# CANreader-XL.net
KiCad netlist of a schematic drawn in EAGLE
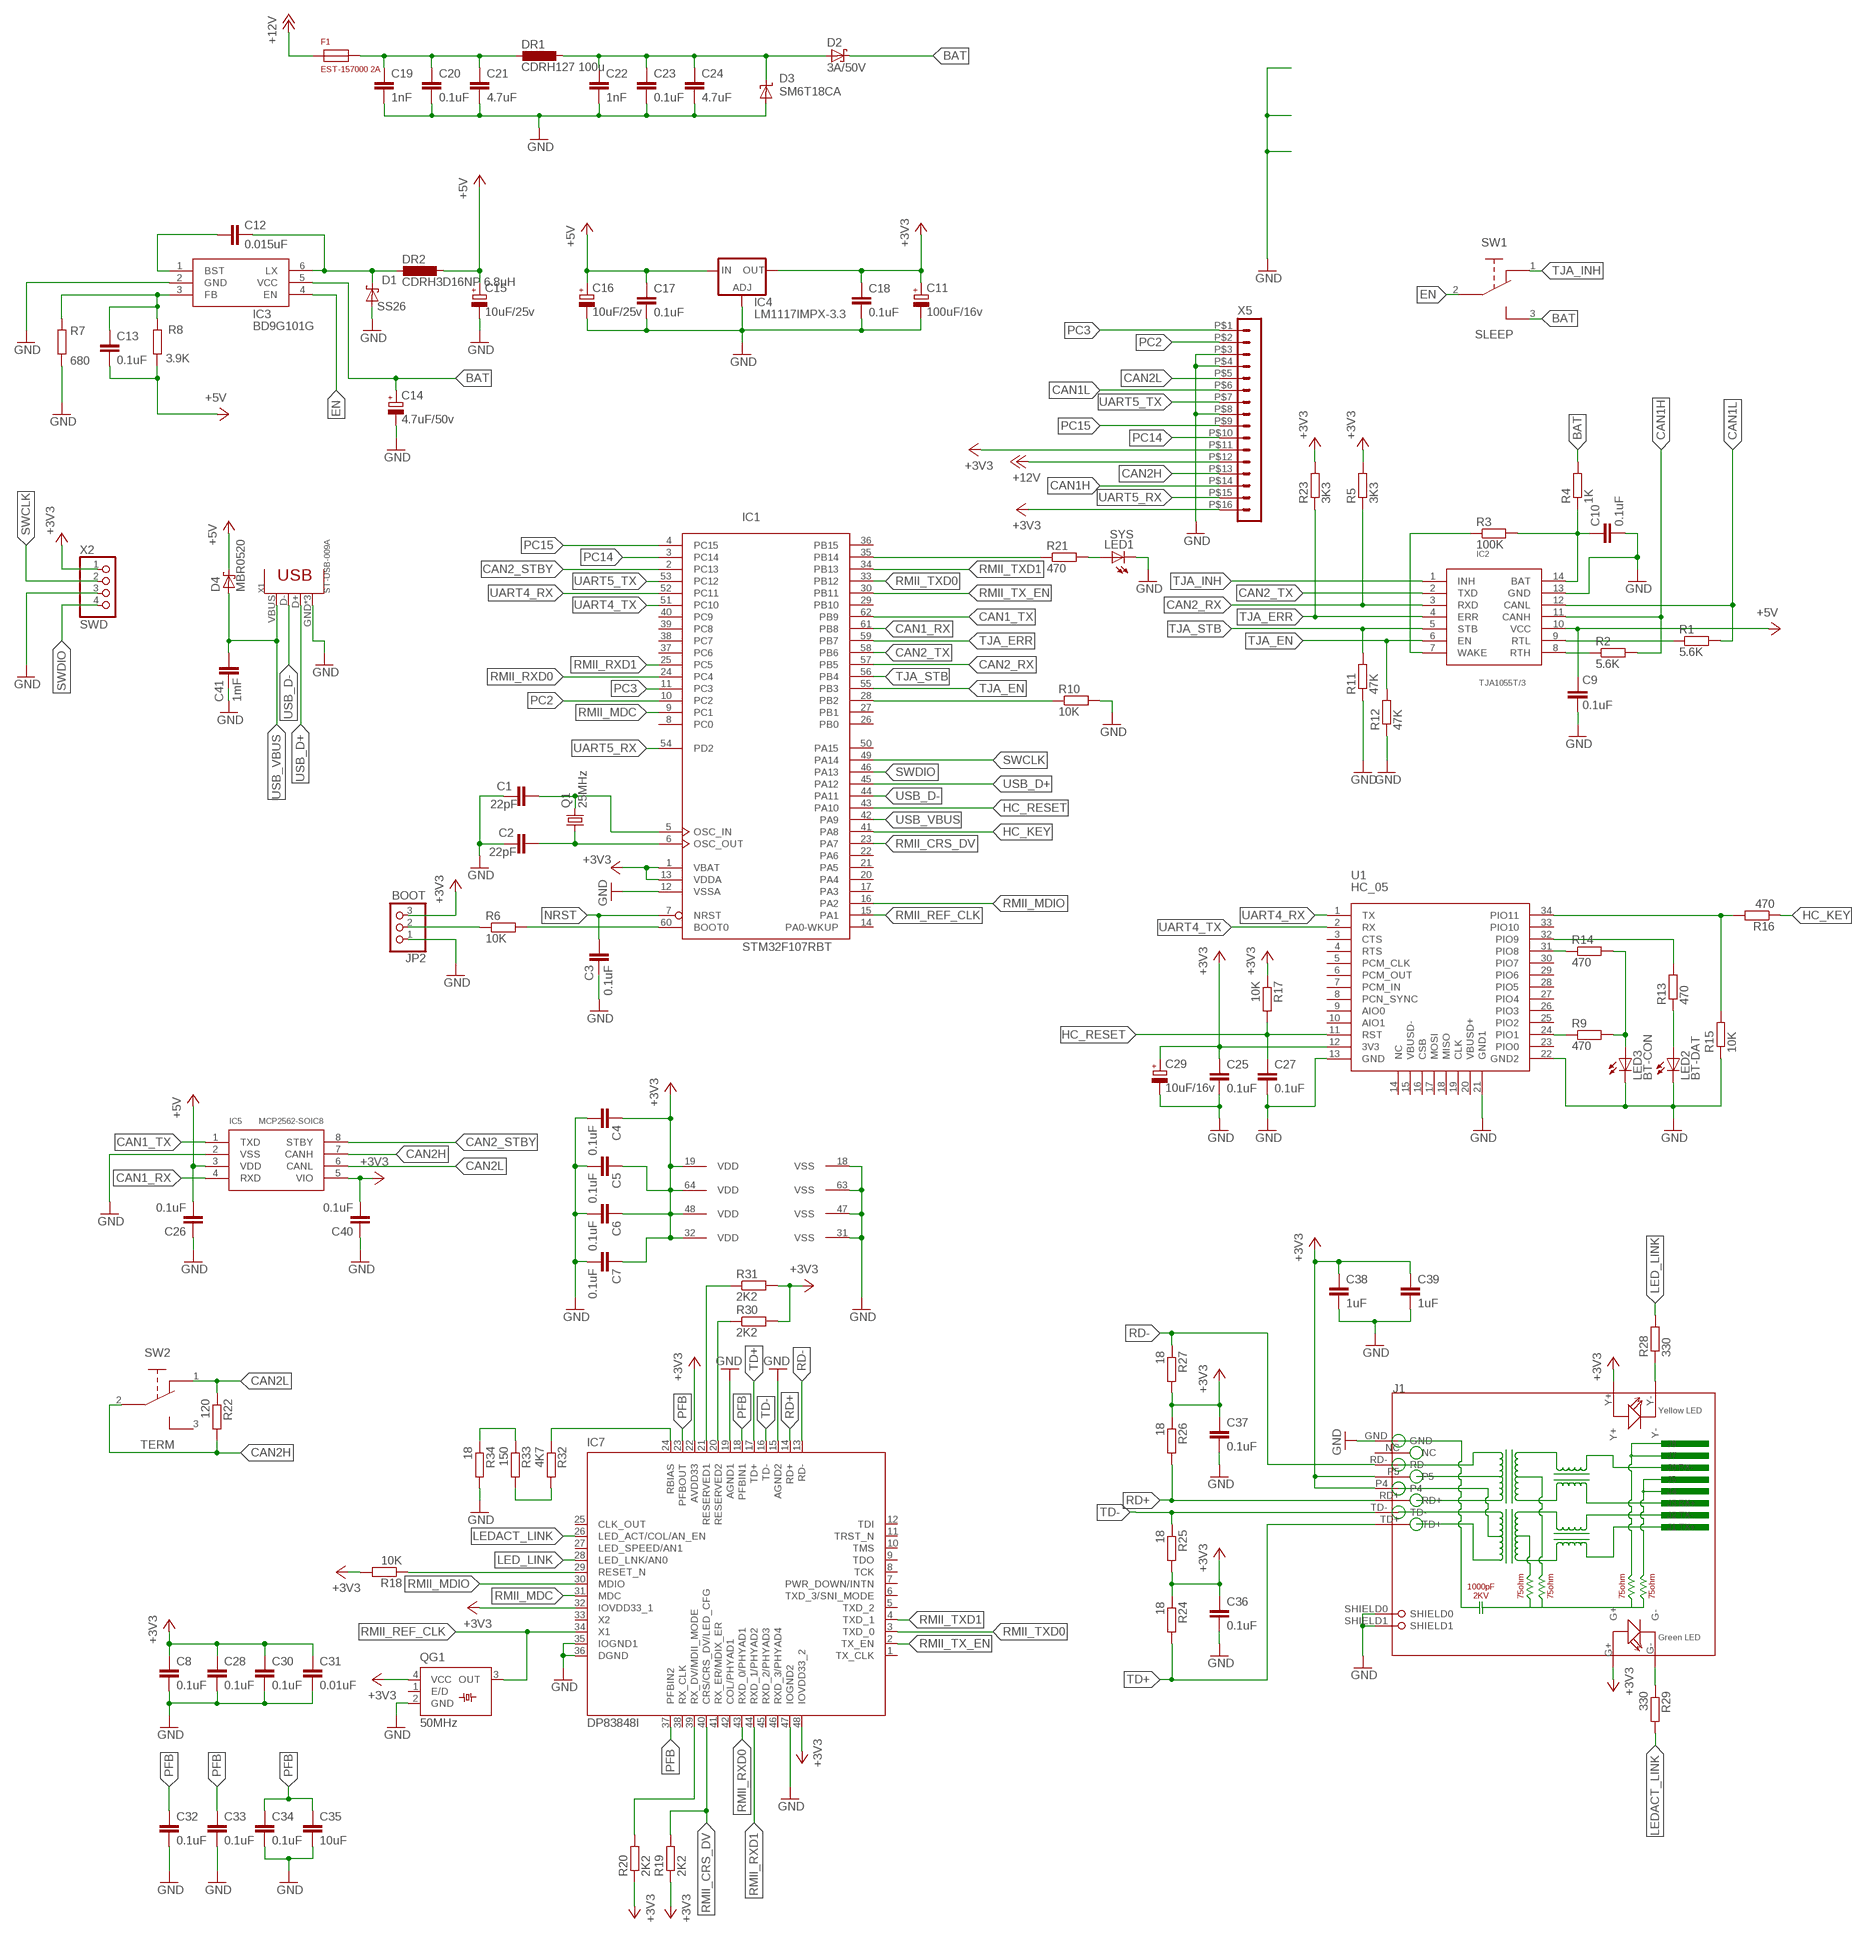
[diagram p0: schematic, sheet 1]

(export (version "E")
  (design (tool "Eeschema 10.0.6"))
  (components
    (comp (ref "C1")
      (value "22pF")
      (footprint "eagle-import:C0805")
      (libsource (lib "eagle-import") (part "C-EUC0805"))
    )
    (comp (ref "C2")
      (value "22pF")
      (footprint "eagle-import:C0805")
      (libsource (lib "eagle-import") (part "C-EUC0805"))
    )
    (comp (ref "C3")
      (value "0.1uF")
      (footprint "eagle-import:C0805")
      (libsource (lib "eagle-import") (part "C-EUC0805"))
    )
    (comp (ref "C4")
      (value "0.1uF")
      (footprint "eagle-import:C0805")
      (libsource (lib "eagle-import") (part "C-EUC0805"))
    )
    (comp (ref "C5")
      (value "0.1uF")
      (footprint "eagle-import:C0805")
      (libsource (lib "eagle-import") (part "C-EUC0805"))
    )
    (comp (ref "C6")
      (value "0.1uF")
      (footprint "eagle-import:C0805")
      (libsource (lib "eagle-import") (part "C-EUC0805"))
    )
    (comp (ref "C7")
      (value "0.1uF")
      (footprint "eagle-import:C0805")
      (libsource (lib "eagle-import") (part "C-EUC0805"))
    )
    (comp (ref "C8")
      (value "0.1uF")
      (footprint "eagle-import:C0805")
      (libsource (lib "eagle-import") (part "C-EUC0805"))
    )
    (comp (ref "C9")
      (value "0.1uF")
      (footprint "eagle-import:C0805")
      (libsource (lib "eagle-import") (part "C-EUC0805"))
    )
    (comp (ref "C10")
      (value "0.1uF")
      (footprint "eagle-import:C0805")
      (libsource (lib "eagle-import") (part "C-EUC0805"))
    )
    (comp (ref "C11")
      (value "100uF/16v")
      (footprint "eagle-import:SMC_D")
      (libsource (lib "eagle-import") (part "CPOL-EUSMCD"))
    )
    (comp (ref "C12")
      (value "0.015uF")
      (footprint "eagle-import:C0805")
      (libsource (lib "eagle-import") (part "C-EUC0805"))
    )
    (comp (ref "C13")
      (value "0.1uF")
      (footprint "eagle-import:C0805")
      (libsource (lib "eagle-import") (part "C-EUC0805"))
    )
    (comp (ref "C14")
      (value "4.7uF/50v")
      (footprint "eagle-import:153CLV-0505")
      (libsource (lib "eagle-import") (part "CPOL-EU153CLV-0505"))
    )
    (comp (ref "C15")
      (value "10uF/25v")
      (footprint "eagle-import:SMC_C")
      (libsource (lib "eagle-import") (part "CPOL-EUSMCC"))
    )
    (comp (ref "C16")
      (value "10uF/25v")
      (footprint "eagle-import:SMC_C")
      (libsource (lib "eagle-import") (part "CPOL-EUSMCC"))
    )
    (comp (ref "C17")
      (value "0.1uF")
      (footprint "eagle-import:C0805")
      (libsource (lib "eagle-import") (part "C-EUC0805"))
    )
    (comp (ref "C18")
      (value "0.1uF")
      (footprint "eagle-import:C0805")
      (libsource (lib "eagle-import") (part "C-EUC0805"))
    )
    (comp (ref "C19")
      (value "1nF")
      (footprint "eagle-import:C0805")
      (libsource (lib "eagle-import") (part "C-EUC0805"))
    )
    (comp (ref "C20")
      (value "0.1uF")
      (footprint "eagle-import:C0805")
      (libsource (lib "eagle-import") (part "C-EUC0805"))
    )
    (comp (ref "C21")
      (value "4.7uF")
      (footprint "eagle-import:C0805")
      (libsource (lib "eagle-import") (part "C-EUC0805"))
    )
    (comp (ref "C22")
      (value "1nF")
      (footprint "eagle-import:C0805")
      (libsource (lib "eagle-import") (part "C-EUC0805"))
    )
    (comp (ref "C23")
      (value "0.1uF")
      (footprint "eagle-import:C0805")
      (libsource (lib "eagle-import") (part "C-EUC0805"))
    )
    (comp (ref "C24")
      (value "4.7uF")
      (footprint "eagle-import:C0805")
      (libsource (lib "eagle-import") (part "C-EUC0805"))
    )
    (comp (ref "C25")
      (value "0.1uF")
      (footprint "eagle-import:C0805")
      (libsource (lib "eagle-import") (part "C-EUC0805"))
    )
    (comp (ref "C26")
      (value "0.1uF")
      (footprint "eagle-import:C0805")
      (libsource (lib "eagle-import") (part "C-EUC0805"))
    )
    (comp (ref "C27")
      (value "0.1uF")
      (footprint "eagle-import:C0805")
      (libsource (lib "eagle-import") (part "C-EUC0805"))
    )
    (comp (ref "C28")
      (value "0.1uF")
      (footprint "eagle-import:C0805")
      (libsource (lib "eagle-import") (part "C-EUC0805"))
    )
    (comp (ref "C29")
      (value "10uF/16v")
      (footprint "eagle-import:SMC_A")
      (libsource (lib "eagle-import") (part "CPOL-EUSMCA"))
    )
    (comp (ref "C30")
      (value "0.1uF")
      (footprint "eagle-import:C0805")
      (libsource (lib "eagle-import") (part "C-EUC0805"))
    )
    (comp (ref "C31")
      (value "0.01uF")
      (footprint "eagle-import:C0805")
      (libsource (lib "eagle-import") (part "C-EUC0805"))
    )
    (comp (ref "C32")
      (value "0.1uF")
      (footprint "eagle-import:C0805")
      (libsource (lib "eagle-import") (part "C-EUC0805"))
    )
    (comp (ref "C33")
      (value "0.1uF")
      (footprint "eagle-import:C0805")
      (libsource (lib "eagle-import") (part "C-EUC0805"))
    )
    (comp (ref "C34")
      (value "0.1uF")
      (footprint "eagle-import:C0805")
      (libsource (lib "eagle-import") (part "C-EUC0805"))
    )
    (comp (ref "C35")
      (value "10uF")
      (footprint "eagle-import:C0805")
      (libsource (lib "eagle-import") (part "C-EUC0805"))
    )
    (comp (ref "C36")
      (value "0.1uF")
      (footprint "eagle-import:C0805")
      (libsource (lib "eagle-import") (part "C-EUC0805"))
    )
    (comp (ref "C37")
      (value "0.1uF")
      (footprint "eagle-import:C0805")
      (libsource (lib "eagle-import") (part "C-EUC0805"))
    )
    (comp (ref "C38")
      (value "1uF")
      (footprint "eagle-import:C0805")
      (libsource (lib "eagle-import") (part "C-EUC0805"))
    )
    (comp (ref "C39")
      (value "1uF")
      (footprint "eagle-import:C0805")
      (libsource (lib "eagle-import") (part "C-EUC0805"))
    )
    (comp (ref "C40")
      (value "0.1uF")
      (footprint "eagle-import:C0805")
      (libsource (lib "eagle-import") (part "C-EUC0805"))
    )
    (comp (ref "C41")
      (value "1mF")
      (footprint "eagle-import:C0805")
      (libsource (lib "eagle-import") (part "C-EUC0805"))
    )
    (comp (ref "D1")
      (value "SS26")
      (footprint "eagle-import:SMB")
      (libsource (lib "eagle-import") (part "SCHOTTKY-DIODESMD"))
    )
    (comp (ref "D2")
      (value "3A/50V")
      (footprint "eagle-import:SMC")
      (libsource (lib "eagle-import") (part "diode_SCHOTTKY-DIODESMC"))
    )
    (comp (ref "D3")
      (value "SM6T18CA")
      (footprint "eagle-import:SMBJ")
      (libsource (lib "eagle-import") (part "SUPPRESSOR-SMBJ"))
    )
    (comp (ref "D4")
      (value "MBR0520")
      (footprint "eagle-import:SOD123")
      (libsource (lib "eagle-import") (part "MBR0520"))
    )
    (comp (ref "DR1")
      (value "CDRH127 100u")
      (footprint "eagle-import:MS85")
      (libsource (lib "eagle-import") (part "CDRH127"))
    )
    (comp (ref "DR2")
      (value "CDRH3D16NP 6.8uH")
      (footprint "eagle-import:CDRH3D16NP")
      (libsource (lib "eagle-import") (part "CDRH3D16NP"))
    )
    (comp (ref "F1")
      (value "EST-157000 2A")
      (footprint "eagle-import:FUSE")
      (libsource (lib "eagle-import") (part "FUSE"))
    )
    (comp (ref "IC1")
      (value "STM32F107RBT")
      (footprint "eagle-import:LQFP64")
      (libsource (lib "eagle-import") (part "STM32F107RTB"))
    )
    (comp (ref "IC2")
      (value "TJA1055T/3")
      (footprint "eagle-import:SO-14W")
      (libsource (lib "eagle-import") (part "TJA1054T"))
    )
    (comp (ref "IC3")
      (value "BD9G101G")
      (footprint "eagle-import:SSOP6")
      (libsource (lib "eagle-import") (part "BD9G101G"))
    )
    (comp (ref "IC4")
      (value "LM1117IMPX-3.3")
      (footprint "eagle-import:SOT223")
      (libsource (lib "eagle-import") (part "LM1117IMPX-3.3"))
    )
    (comp (ref "IC5")
      (value "MCP2562-SOIC8")
      (footprint "eagle-import:SOIC8-1.27-5X4MM")
      (libsource (lib "eagle-import") (part "MCP2562-SOIC8"))
    )
    (comp (ref "IC7")
      (value "DP83848I")
      (footprint "eagle-import:LQFP48")
      (fields (field (name "MPN") "DP83848VYB"))
      (libsource (lib "eagle-import") (part "DP83848I"))
    )
    (comp (ref "J1")
      (value "RJ45-HR911105A-HR911105A")
      (footprint "eagle-import:RJ45")
      (libsource (lib "eagle-import") (part "RJ45-HR911105A-HR911105A"))
    )
    (comp (ref "JP2")
      (value "BOOT")
      (footprint "eagle-import:1X03")
      (libsource (lib "eagle-import") (part "PINHD-1X3"))
    )
    (comp (ref "LED1")
      (value "SYS")
      (footprint "eagle-import:LED3MM")
      (libsource (lib "eagle-import") (part "LED3MM"))
    )
    (comp (ref "LED2")
      (value "BT-DAT")
      (footprint "eagle-import:LED3MM")
      (libsource (lib "eagle-import") (part "LED3MM"))
    )
    (comp (ref "LED3")
      (value "BT-CON")
      (footprint "eagle-import:LED3MM")
      (libsource (lib "eagle-import") (part "LED3MM"))
    )
    (comp (ref "Q1")
      (value "25MHz")
      (footprint "eagle-import:HC49_S")
      (libsource (lib "eagle-import") (part "CRYSTALHC49S"))
    )
    (comp (ref "QG1")
      (value "50MHz")
      (footprint "eagle-import:SM77H")
      (libsource (lib "eagle-import") (part "SM77H"))
    )
    (comp (ref "R1")
      (value "5.6K")
      (footprint "eagle-import:R0805")
      (libsource (lib "eagle-import") (part "R-EU_R0805"))
    )
    (comp (ref "R2")
      (value "5.6K")
      (footprint "eagle-import:R0805")
      (libsource (lib "eagle-import") (part "R-EU_R0805"))
    )
    (comp (ref "R3")
      (value "100K")
      (footprint "eagle-import:R0805")
      (libsource (lib "eagle-import") (part "R-EU_R0805"))
    )
    (comp (ref "R4")
      (value "1K")
      (footprint "eagle-import:R0805")
      (libsource (lib "eagle-import") (part "R-EU_R0805"))
    )
    (comp (ref "R5")
      (value "3K3")
      (footprint "eagle-import:R0805")
      (libsource (lib "eagle-import") (part "R-EU_R0805"))
    )
    (comp (ref "R6")
      (value "10K")
      (footprint "eagle-import:R0805")
      (libsource (lib "eagle-import") (part "R-EU_R0805"))
    )
    (comp (ref "R7")
      (value "680")
      (footprint "eagle-import:R0805")
      (libsource (lib "eagle-import") (part "R-EU_R0805"))
    )
    (comp (ref "R8")
      (value "3.9K")
      (footprint "eagle-import:R0805")
      (libsource (lib "eagle-import") (part "R-EU_R0805"))
    )
    (comp (ref "R9")
      (value "470")
      (footprint "eagle-import:R0805")
      (libsource (lib "eagle-import") (part "R-EU_R0805"))
    )
    (comp (ref "R10")
      (value "10K")
      (footprint "eagle-import:R0805")
      (libsource (lib "eagle-import") (part "R-EU_R0805"))
    )
    (comp (ref "R11")
      (value "47K")
      (footprint "eagle-import:R0805")
      (libsource (lib "eagle-import") (part "R-EU_R0805"))
    )
    (comp (ref "R12")
      (value "47K")
      (footprint "eagle-import:R0805")
      (libsource (lib "eagle-import") (part "R-EU_R0805"))
    )
    (comp (ref "R13")
      (value "470")
      (footprint "eagle-import:R0805")
      (libsource (lib "eagle-import") (part "R-EU_R0805"))
    )
    (comp (ref "R14")
      (value "470")
      (footprint "eagle-import:R0805")
      (libsource (lib "eagle-import") (part "R-EU_R0805"))
    )
    (comp (ref "R15")
      (value "10K")
      (footprint "eagle-import:R0805")
      (libsource (lib "eagle-import") (part "R-EU_R0805"))
    )
    (comp (ref "R16")
      (value "470")
      (footprint "eagle-import:R0805")
      (libsource (lib "eagle-import") (part "R-EU_R0805"))
    )
    (comp (ref "R17")
      (value "10K")
      (footprint "eagle-import:R0805")
      (libsource (lib "eagle-import") (part "R-EU_R0805"))
    )
    (comp (ref "R18")
      (value "10K")
      (footprint "eagle-import:R0805")
      (libsource (lib "eagle-import") (part "R-EU_R0805"))
    )
    (comp (ref "R19")
      (value "2K2")
      (footprint "eagle-import:R0805")
      (libsource (lib "eagle-import") (part "R-EU_R0805"))
    )
    (comp (ref "R20")
      (value "2K2")
      (footprint "eagle-import:R0805")
      (libsource (lib "eagle-import") (part "R-EU_R0805"))
    )
    (comp (ref "R21")
      (value "470")
      (footprint "eagle-import:R0805")
      (libsource (lib "eagle-import") (part "R-EU_R0805"))
    )
    (comp (ref "R22")
      (value "120")
      (footprint "eagle-import:R0805")
      (libsource (lib "eagle-import") (part "R-EU_R0805"))
    )
    (comp (ref "R23")
      (value "3K3")
      (footprint "eagle-import:R0805")
      (libsource (lib "eagle-import") (part "R-EU_R0805"))
    )
    (comp (ref "R24")
      (value "18")
      (footprint "eagle-import:R0805")
      (libsource (lib "eagle-import") (part "R-EU_R0805"))
    )
    (comp (ref "R25")
      (value "18")
      (footprint "eagle-import:R0805")
      (libsource (lib "eagle-import") (part "R-EU_R0805"))
    )
    (comp (ref "R26")
      (value "18")
      (footprint "eagle-import:R0805")
      (libsource (lib "eagle-import") (part "R-EU_R0805"))
    )
    (comp (ref "R27")
      (value "18")
      (footprint "eagle-import:R0805")
      (libsource (lib "eagle-import") (part "R-EU_R0805"))
    )
    (comp (ref "R28")
      (value "330")
      (footprint "eagle-import:R0805")
      (libsource (lib "eagle-import") (part "R-EU_R0805"))
    )
    (comp (ref "R29")
      (value "330")
      (footprint "eagle-import:R0805")
      (libsource (lib "eagle-import") (part "R-EU_R0805"))
    )
    (comp (ref "R30")
      (value "2K2")
      (footprint "eagle-import:R0805")
      (libsource (lib "eagle-import") (part "R-EU_R0805"))
    )
    (comp (ref "R31")
      (value "2K2")
      (footprint "eagle-import:R0805")
      (libsource (lib "eagle-import") (part "R-EU_R0805"))
    )
    (comp (ref "R32")
      (value "4K7")
      (footprint "eagle-import:R0805")
      (libsource (lib "eagle-import") (part "R-EU_R0805"))
    )
    (comp (ref "R33")
      (value "150")
      (footprint "eagle-import:R0805")
      (libsource (lib "eagle-import") (part "R-EU_R0805"))
    )
    (comp (ref "R34")
      (value "18")
      (footprint "eagle-import:R0805")
      (libsource (lib "eagle-import") (part "R-EU_R0805"))
    )
    (comp (ref "SW1")
      (value "SLEEP")
      (footprint "eagle-import:SS12F27")
      (libsource (lib "eagle-import") (part "SS12F27"))
    )
    (comp (ref "SW2")
      (value "TERM")
      (footprint "eagle-import:SS12F27")
      (libsource (lib "eagle-import") (part "SS12F27"))
    )
    (comp (ref "U1")
      (value "HC_05")
      (footprint "eagle-import:BLUETOOTH_SMD")
      (libsource (lib "eagle-import") (part "HC_05"))
    )
    (comp (ref "X1")
      (value "ST-USB-009A")
      (footprint "eagle-import:USB4+2-2.5-90D")
      (libsource (lib "eagle-import") (part "DIP-USB-B-TYPE-FMAL(4+2P-2.5-90D)"))
    )
    (comp (ref "X2")
      (value "SWD")
      (footprint "eagle-import:1X04")
      (libsource (lib "eagle-import") (part "PINHD-1X4"))
    )
    (comp (ref "X5")
      (value "HEADER_POS16_43045-1600")
      (footprint "eagle-import:43045-1600")
      (libsource (lib "eagle-import") (part "HEADER_POS16_?43045-1600"))
    )
  )
  (nets
    (net (code "1") (name "+3V3") (class "Default")
      (node (ref "C11") (pin "+") (pinfunction "+_+") (pintype "passive"))
      (node (ref "C18") (pin "1") (pinfunction "1_1") (pintype "passive"))
      (node (ref "C25") (pin "1") (pinfunction "1_1") (pintype "passive"))
      (node (ref "C28") (pin "1") (pinfunction "1_1") (pintype "passive"))
      (node (ref "C29") (pin "+") (pinfunction "+_+") (pintype "passive"))
      (node (ref "C30") (pin "1") (pinfunction "1_1") (pintype "passive"))
      (node (ref "C31") (pin "1") (pinfunction "1_1") (pintype "passive"))
      (node (ref "C36") (pin "1") (pinfunction "1_1") (pintype "passive"))
      (node (ref "C37") (pin "1") (pinfunction "1_1") (pintype "passive"))
      (node (ref "C38") (pin "1") (pinfunction "1_1") (pintype "passive"))
      (node (ref "C39") (pin "1") (pinfunction "1_1") (pintype "passive"))
      (node (ref "C4") (pin "1") (pinfunction "1_1") (pintype "passive"))
      (node (ref "C40") (pin "2") (pinfunction "2_2") (pintype "passive"))
      (node (ref "C5") (pin "1") (pinfunction "1_1") (pintype "passive"))
      (node (ref "C6") (pin "1") (pinfunction "1_1") (pintype "passive"))
      (node (ref "C7") (pin "1") (pinfunction "1_1") (pintype "passive"))
      (node (ref "C8") (pin "1") (pinfunction "1_1") (pintype "passive"))
      (node (ref "IC1") (pin "1") (pinfunction "VBAT_1") (pintype "power_in"))
      (node (ref "IC1") (pin "13") (pinfunction "VDDA_13") (pintype "power_in"))
      (node (ref "IC1") (pin "19") (pinfunction "VDD_19") (pintype "power_in"))
      (node (ref "IC1") (pin "32") (pinfunction "VDD_32") (pintype "power_in"))
      (node (ref "IC1") (pin "48") (pinfunction "VDD_48") (pintype "power_in"))
      (node (ref "IC1") (pin "64") (pinfunction "VDD_64") (pintype "power_in"))
      (node (ref "IC4") (pin "2") (pinfunction "OUT_2") (pintype "passive"))
      (node (ref "IC4") (pin "4") (pinfunction "OUT_4") (pintype "passive"))
      (node (ref "IC5") (pin "5") (pinfunction "VIO_5") (pintype "power_in"))
      (node (ref "IC7") (pin "22") (pinfunction "AVDD33_22") (pintype "power_in"))
      (node (ref "IC7") (pin "32") (pinfunction "IOVDD33_1_32") (pintype "power_in"))
      (node (ref "IC7") (pin "48") (pinfunction "IOVDD33_2_48") (pintype "power_in"))
      (node (ref "J1") (pin "G+") (pinfunction "G+_G+") (pintype "bidirectional"))
      (node (ref "J1") (pin "P4") (pinfunction "P4_P4") (pintype "bidirectional"))
      (node (ref "J1") (pin "P5") (pinfunction "P5_P5") (pintype "bidirectional"))
      (node (ref "J1") (pin "Y+") (pinfunction "Y+_Y+") (pintype "bidirectional"))
      (node (ref "JP2") (pin "3") (pinfunction "3_3") (pintype "passive"))
      (node (ref "QG1") (pin "4") (pinfunction "VCC_4") (pintype "power_in"))
      (node (ref "R17") (pin "1") (pinfunction "1_1") (pintype "passive"))
      (node (ref "R18") (pin "2") (pinfunction "2_2") (pintype "passive"))
      (node (ref "R19") (pin "1") (pinfunction "1_1") (pintype "passive"))
      (node (ref "R20") (pin "1") (pinfunction "1_1") (pintype "passive"))
      (node (ref "R23") (pin "2") (pinfunction "2_2") (pintype "passive"))
      (node (ref "R24") (pin "1") (pinfunction "1_1") (pintype "passive"))
      (node (ref "R25") (pin "2") (pinfunction "2_2") (pintype "passive"))
      (node (ref "R26") (pin "1") (pinfunction "1_1") (pintype "passive"))
      (node (ref "R27") (pin "2") (pinfunction "2_2") (pintype "passive"))
      (node (ref "R30") (pin "2") (pinfunction "2_2") (pintype "passive"))
      (node (ref "R31") (pin "2") (pinfunction "2_2") (pintype "passive"))
      (node (ref "R5") (pin "2") (pinfunction "2_2") (pintype "passive"))
      (node (ref "U1") (pin "12") (pinfunction "3V3_12") (pintype "bidirectional"))
      (node (ref "X2") (pin "1") (pinfunction "1_1") (pintype "passive"))
      (node (ref "X5") (pin "P$11") (pinfunction "11_P$11") (pintype "passive"))
      (node (ref "X5") (pin "P$16") (pinfunction "16_P$16") (pintype "passive"))
    )
    (net (code "2") (name "+5V") (class "Default")
      (node (ref "C13") (pin "2") (pinfunction "2_2") (pintype "passive"))
      (node (ref "C15") (pin "+") (pinfunction "+_+") (pintype "passive"))
      (node (ref "C16") (pin "+") (pinfunction "+_+") (pintype "passive"))
      (node (ref "C17") (pin "1") (pinfunction "1_1") (pintype "passive"))
      (node (ref "C26") (pin "2") (pinfunction "2_2") (pintype "passive"))
      (node (ref "C9") (pin "1") (pinfunction "1_1") (pintype "passive"))
      (node (ref "D4") (pin "C") (pinfunction "C_C") (pintype "passive"))
      (node (ref "DR2") (pin "P$2") (pinfunction "2_P$2") (pintype "passive"))
      (node (ref "IC2") (pin "10") (pinfunction "VCC_10") (pintype "power_in"))
      (node (ref "IC4") (pin "3") (pinfunction "IN_3") (pintype "input"))
      (node (ref "IC5") (pin "3") (pinfunction "VDD_3") (pintype "power_in"))
      (node (ref "R8") (pin "1") (pinfunction "1_1") (pintype "passive"))
    )
    (net (code "3") (name "+12V") (class "Default")
      (node (ref "F1") (pin "P$1") (pinfunction "1_P$1") (pintype "power_in"))
      (node (ref "X5") (pin "P$12") (pinfunction "12_P$12") (pintype "passive"))
    )
    (net (code "4") (name "BAT") (class "Default")
      (node (ref "C14") (pin "+") (pinfunction "+_+") (pintype "passive"))
      (node (ref "D2") (pin "C") (pinfunction "C_C") (pintype "passive"))
      (node (ref "IC3") (pin "5") (pinfunction "VCC_5") (pintype "power_in"))
      (node (ref "R4") (pin "2") (pinfunction "2_2") (pintype "passive"))
      (node (ref "SW1") (pin "3") (pinfunction "3_3") (pintype "bidirectional"))
    )
    (net (code "5") (name "CAN1H") (class "Default")
      (node (ref "IC2") (pin "11") (pinfunction "CANH_11") (pintype "bidirectional"))
      (node (ref "R2") (pin "2") (pinfunction "2_2") (pintype "passive"))
      (node (ref "X5") (pin "P$14") (pinfunction "14_P$14") (pintype "passive"))
    )
    (net (code "6") (name "CAN1L") (class "Default")
      (node (ref "IC2") (pin "12") (pinfunction "CANL_12") (pintype "bidirectional"))
      (node (ref "R1") (pin "2") (pinfunction "2_2") (pintype "passive"))
      (node (ref "X5") (pin "P$6") (pinfunction "6_P$6") (pintype "passive"))
    )
    (net (code "7") (name "CAN1_RX") (class "Default")
      (node (ref "IC1") (pin "61") (pinfunction "PB8_61") (pintype "bidirectional"))
      (node (ref "IC5") (pin "4") (pinfunction "RXD_4") (pintype "output"))
    )
    (net (code "8") (name "CAN1_TX") (class "Default")
      (node (ref "IC1") (pin "62") (pinfunction "PB9_62") (pintype "bidirectional"))
      (node (ref "IC5") (pin "1") (pinfunction "TXD_1") (pintype "input"))
    )
    (net (code "9") (name "CAN2H") (class "Default")
      (node (ref "IC5") (pin "7") (pinfunction "CANH_7") (pintype "bidirectional"))
      (node (ref "R22") (pin "2") (pinfunction "2_2") (pintype "passive"))
      (node (ref "SW2") (pin "2") (pinfunction "2_2") (pintype "bidirectional"))
      (node (ref "X5") (pin "P$13") (pinfunction "13_P$13") (pintype "passive"))
    )
    (net (code "10") (name "CAN2L") (class "Default")
      (node (ref "IC5") (pin "6") (pinfunction "CANL_6") (pintype "bidirectional"))
      (node (ref "R22") (pin "1") (pinfunction "1_1") (pintype "passive"))
      (node (ref "SW2") (pin "1") (pinfunction "1_1") (pintype "bidirectional"))
      (node (ref "X5") (pin "P$5") (pinfunction "5_P$5") (pintype "passive"))
    )
    (net (code "11") (name "CAN2_RX") (class "Default")
      (node (ref "IC1") (pin "57") (pinfunction "PB5_57") (pintype "bidirectional"))
      (node (ref "IC2") (pin "3") (pinfunction "RXD_3") (pintype "bidirectional"))
      (node (ref "R5") (pin "1") (pinfunction "1_1") (pintype "passive"))
    )
    (net (code "12") (name "CAN2_STBY") (class "Default")
      (node (ref "IC1") (pin "2") (pinfunction "PC13_2") (pintype "bidirectional"))
      (node (ref "IC5") (pin "8") (pinfunction "STBY_8") (pintype "input"))
    )
    (net (code "13") (name "CAN2_TX") (class "Default")
      (node (ref "IC1") (pin "58") (pinfunction "PB6_58") (pintype "bidirectional"))
      (node (ref "IC2") (pin "2") (pinfunction "TXD_2") (pintype "bidirectional"))
    )
    (net (code "14") (name "EN") (class "Default")
      (node (ref "IC3") (pin "4") (pinfunction "EN_4") (pintype "input"))
      (node (ref "SW1") (pin "2") (pinfunction "2_2") (pintype "bidirectional"))
    )
    (net (code "15") (name "GND") (class "Default")
      (node (ref "C1") (pin "2") (pinfunction "2_2") (pintype "passive"))
      (node (ref "C10") (pin "2") (pinfunction "2_2") (pintype "passive"))
      (node (ref "C11") (pin "-") (pinfunction "-_-") (pintype "passive"))
      (node (ref "C14") (pin "-") (pinfunction "-_-") (pintype "passive"))
      (node (ref "C15") (pin "-") (pinfunction "-_-") (pintype "passive"))
      (node (ref "C16") (pin "-") (pinfunction "-_-") (pintype "passive"))
      (node (ref "C17") (pin "2") (pinfunction "2_2") (pintype "passive"))
      (node (ref "C18") (pin "2") (pinfunction "2_2") (pintype "passive"))
      (node (ref "C19") (pin "2") (pinfunction "2_2") (pintype "passive"))
      (node (ref "C2") (pin "2") (pinfunction "2_2") (pintype "passive"))
      (node (ref "C20") (pin "2") (pinfunction "2_2") (pintype "passive"))
      (node (ref "C21") (pin "2") (pinfunction "2_2") (pintype "passive"))
      (node (ref "C22") (pin "2") (pinfunction "2_2") (pintype "passive"))
      (node (ref "C23") (pin "2") (pinfunction "2_2") (pintype "passive"))
      (node (ref "C24") (pin "2") (pinfunction "2_2") (pintype "passive"))
      (node (ref "C25") (pin "2") (pinfunction "2_2") (pintype "passive"))
      (node (ref "C26") (pin "1") (pinfunction "1_1") (pintype "passive"))
      (node (ref "C27") (pin "2") (pinfunction "2_2") (pintype "passive"))
      (node (ref "C28") (pin "2") (pinfunction "2_2") (pintype "passive"))
      (node (ref "C29") (pin "-") (pinfunction "-_-") (pintype "passive"))
      (node (ref "C3") (pin "1") (pinfunction "1_1") (pintype "passive"))
      (node (ref "C30") (pin "2") (pinfunction "2_2") (pintype "passive"))
      (node (ref "C31") (pin "2") (pinfunction "2_2") (pintype "passive"))
      (node (ref "C32") (pin "2") (pinfunction "2_2") (pintype "passive"))
      (node (ref "C33") (pin "2") (pinfunction "2_2") (pintype "passive"))
      (node (ref "C34") (pin "2") (pinfunction "2_2") (pintype "passive"))
      (node (ref "C35") (pin "2") (pinfunction "2_2") (pintype "passive"))
      (node (ref "C36") (pin "2") (pinfunction "2_2") (pintype "passive"))
      (node (ref "C37") (pin "2") (pinfunction "2_2") (pintype "passive"))
      (node (ref "C38") (pin "2") (pinfunction "2_2") (pintype "passive"))
      (node (ref "C39") (pin "2") (pinfunction "2_2") (pintype "passive"))
      (node (ref "C4") (pin "2") (pinfunction "2_2") (pintype "passive"))
      (node (ref "C40") (pin "1") (pinfunction "1_1") (pintype "passive"))
      (node (ref "C41") (pin "2") (pinfunction "2_2") (pintype "passive"))
      (node (ref "C5") (pin "2") (pinfunction "2_2") (pintype "passive"))
      (node (ref "C6") (pin "2") (pinfunction "2_2") (pintype "passive"))
      (node (ref "C7") (pin "2") (pinfunction "2_2") (pintype "passive"))
      (node (ref "C8") (pin "2") (pinfunction "2_2") (pintype "passive"))
      (node (ref "C9") (pin "2") (pinfunction "2_2") (pintype "passive"))
      (node (ref "D1") (pin "A") (pinfunction "A_A") (pintype "passive"))
      (node (ref "D3") (pin "A") (pinfunction "A_A") (pintype "passive"))
      (node (ref "IC1") (pin "12") (pinfunction "VSSA_12") (pintype "power_in"))
      (node (ref "IC1") (pin "18") (pinfunction "VSS_18") (pintype "power_in"))
      (node (ref "IC1") (pin "31") (pinfunction "VSS_31") (pintype "power_in"))
      (node (ref "IC1") (pin "47") (pinfunction "VSS_47") (pintype "power_in"))
      (node (ref "IC1") (pin "63") (pinfunction "VSS_63") (pintype "power_in"))
      (node (ref "IC2") (pin "13") (pinfunction "GND_13") (pintype "power_in"))
      (node (ref "IC3") (pin "2") (pinfunction "GND_2") (pintype "power_in"))
      (node (ref "IC4") (pin "1") (pinfunction "ADJ_1") (pintype "input"))
      (node (ref "IC5") (pin "2") (pinfunction "VSS_2") (pintype "power_in"))
      (node (ref "IC7") (pin "15") (pinfunction "AGND2_15") (pintype "power_in"))
      (node (ref "IC7") (pin "19") (pinfunction "AGND1_19") (pintype "power_in"))
      (node (ref "IC7") (pin "35") (pinfunction "IOGND1_35") (pintype "power_in"))
      (node (ref "IC7") (pin "36") (pinfunction "DGND_36") (pintype "power_in"))
      (node (ref "IC7") (pin "47") (pinfunction "IOGND2_47") (pintype "power_in"))
      (node (ref "J1") (pin "GND") (pinfunction "GND_GND") (pintype "bidirectional"))
      (node (ref "J1") (pin "SHIELD0") (pinfunction "SHIELD0_SHIELD0") (pintype "bidirectional"))
      (node (ref "J1") (pin "SHIELD1") (pinfunction "SHIELD1_SHIELD1") (pintype "bidirectional"))
      (node (ref "JP2") (pin "1") (pinfunction "1_1") (pintype "passive"))
      (node (ref "LED1") (pin "K") (pinfunction "C_K") (pintype "passive"))
      (node (ref "LED2") (pin "K") (pinfunction "C_K") (pintype "passive"))
      (node (ref "LED3") (pin "K") (pinfunction "C_K") (pintype "passive"))
      (node (ref "QG1") (pin "2") (pinfunction "GND_2") (pintype "power_in"))
      (node (ref "R10") (pin "2") (pinfunction "2_2") (pintype "passive"))
      (node (ref "R11") (pin "1") (pinfunction "1_1") (pintype "passive"))
      (node (ref "R12") (pin "1") (pinfunction "1_1") (pintype "passive"))
      (node (ref "R15") (pin "1") (pinfunction "1_1") (pintype "passive"))
      (node (ref "R34") (pin "2") (pinfunction "2_2") (pintype "passive"))
      (node (ref "R7") (pin "1") (pinfunction "1_1") (pintype "passive"))
      (node (ref "U1") (pin "13") (pinfunction "GND_13") (pintype "bidirectional"))
      (node (ref "U1") (pin "21") (pinfunction "GND1_21") (pintype "bidirectional"))
      (node (ref "U1") (pin "22") (pinfunction "GND2_22") (pintype "bidirectional"))
      (node (ref "X1") (pin "GND") (pinfunction "4_GND") (pintype "bidirectional"))
      (node (ref "X1") (pin "S1") (pinfunction "4_S1") (pintype "bidirectional"))
      (node (ref "X1") (pin "S2") (pinfunction "4_S2") (pintype "bidirectional"))
      (node (ref "X2") (pin "3") (pinfunction "3_3") (pintype "passive"))
      (node (ref "X5") (pin "P$3") (pinfunction "3_P$3") (pintype "passive"))
      (node (ref "X5") (pin "P$4") (pinfunction "4_P$4") (pintype "passive"))
      (node (ref "X5") (pin "P$8") (pinfunction "8_P$8") (pintype "passive"))
    )
    (net (code "16") (name "HC_KEY") (class "Default")
      (node (ref "IC1") (pin "41") (pinfunction "PA8_41") (pintype "bidirectional"))
      (node (ref "R16") (pin "1") (pinfunction "1_1") (pintype "passive"))
    )
    (net (code "17") (name "HC_RESET") (class "Default")
      (node (ref "C27") (pin "1") (pinfunction "1_1") (pintype "passive"))
      (node (ref "IC1") (pin "43") (pinfunction "PA10_43") (pintype "bidirectional"))
      (node (ref "R17") (pin "2") (pinfunction "2_2") (pintype "passive"))
      (node (ref "U1") (pin "11") (pinfunction "RST_11") (pintype "bidirectional"))
    )
    (net (code "18") (name "LEDACT_LINK") (class "Default")
      (node (ref "IC7") (pin "26") (pinfunction "LED_ACT/COL/AN_EN_26") (pintype "bidirectional"))
      (node (ref "R29") (pin "2") (pinfunction "2_2") (pintype "passive"))
    )
    (net (code "19") (name "LED_LINK") (class "Default")
      (node (ref "IC7") (pin "28") (pinfunction "LED_LNK/AN0_28") (pintype "bidirectional"))
      (node (ref "R28") (pin "2") (pinfunction "2_2") (pintype "passive"))
    )
    (net (code "20") (name "NRST") (class "Default")
      (node (ref "C3") (pin "2") (pinfunction "2_2") (pintype "passive"))
      (node (ref "IC1") (pin "7") (pinfunction "NRST_7") (pintype "bidirectional"))
    )
    (net (code "21") (name "Net-(DR1-1)") (class "Default")
      (node (ref "C19") (pin "1") (pinfunction "1_1") (pintype "passive"))
      (node (ref "C20") (pin "1") (pinfunction "1_1") (pintype "passive"))
      (node (ref "C21") (pin "1") (pinfunction "1_1") (pintype "passive"))
      (node (ref "DR1") (pin "P$1") (pinfunction "1_P$1") (pintype "passive"))
      (node (ref "F1") (pin "P$2") (pinfunction "2_P$2") (pintype "passive"))
    )
    (net (code "22") (name "Net-(DR1-2)") (class "Default")
      (node (ref "C22") (pin "1") (pinfunction "1_1") (pintype "passive"))
      (node (ref "C23") (pin "1") (pinfunction "1_1") (pintype "passive"))
      (node (ref "C24") (pin "1") (pinfunction "1_1") (pintype "passive"))
      (node (ref "D2") (pin "A") (pinfunction "A_A") (pintype "passive"))
      (node (ref "D3") (pin "C") (pinfunction "C_C") (pintype "passive"))
      (node (ref "DR1") (pin "P$2") (pinfunction "2_P$2") (pintype "passive"))
    )
    (net (code "23") (name "Net-(DR2-1)") (class "Default")
      (node (ref "C12") (pin "2") (pinfunction "2_2") (pintype "passive"))
      (node (ref "D1") (pin "C") (pinfunction "C_C") (pintype "passive"))
      (node (ref "DR2") (pin "P$1") (pinfunction "1_P$1") (pintype "passive"))
      (node (ref "IC3") (pin "6") (pinfunction "LX_6") (pintype "output"))
    )
    (net (code "24") (name "Net-(IC1A-BOOT0)") (class "Default")
      (node (ref "IC1") (pin "60") (pinfunction "BOOT0_60") (pintype "input"))
      (node (ref "R6") (pin "2") (pinfunction "2_2") (pintype "passive"))
    )
    (net (code "25") (name "Net-(IC1A-OSC_IN)") (class "Default")
      (node (ref "C1") (pin "1") (pinfunction "1_1") (pintype "passive"))
      (node (ref "IC1") (pin "5") (pinfunction "OSC_IN_5") (pintype "bidirectional"))
      (node (ref "Q1") (pin "2") (pinfunction "2_2") (pintype "passive"))
    )
    (net (code "26") (name "Net-(IC1A-OSC_OUT)") (class "Default")
      (node (ref "C2") (pin "1") (pinfunction "1_1") (pintype "passive"))
      (node (ref "IC1") (pin "6") (pinfunction "OSC_OUT_6") (pintype "bidirectional"))
      (node (ref "Q1") (pin "1") (pinfunction "1_1") (pintype "passive"))
    )
    (net (code "27") (name "Net-(IC1A-PB2)") (class "Default")
      (node (ref "IC1") (pin "28") (pinfunction "PB2_28") (pintype "bidirectional"))
      (node (ref "R10") (pin "1") (pinfunction "1_1") (pintype "passive"))
    )
    (net (code "28") (name "Net-(IC1A-PB14)") (class "Default")
      (node (ref "IC1") (pin "35") (pinfunction "PB14_35") (pintype "bidirectional"))
      (node (ref "R21") (pin "1") (pinfunction "1_1") (pintype "passive"))
    )
    (net (code "29") (name "Net-(IC2-BAT)") (class "Default")
      (node (ref "C10") (pin "1") (pinfunction "1_1") (pintype "passive"))
      (node (ref "IC2") (pin "14") (pinfunction "BAT_14") (pintype "input"))
      (node (ref "R3") (pin "2") (pinfunction "2_2") (pintype "passive"))
      (node (ref "R4") (pin "1") (pinfunction "1_1") (pintype "passive"))
    )
    (net (code "30") (name "Net-(IC2-RTH)") (class "Default")
      (node (ref "IC2") (pin "8") (pinfunction "RTH_8") (pintype "bidirectional"))
      (node (ref "R2") (pin "1") (pinfunction "1_1") (pintype "passive"))
    )
    (net (code "31") (name "Net-(IC2-RTL)") (class "Default")
      (node (ref "IC2") (pin "9") (pinfunction "RTL_9") (pintype "bidirectional"))
      (node (ref "R1") (pin "1") (pinfunction "1_1") (pintype "passive"))
    )
    (net (code "32") (name "Net-(IC2-WAKE)") (class "Default")
      (node (ref "IC2") (pin "7") (pinfunction "WAKE_7") (pintype "input"))
      (node (ref "R3") (pin "1") (pinfunction "1_1") (pintype "passive"))
    )
    (net (code "33") (name "Net-(IC3-BST)") (class "Default")
      (node (ref "C12") (pin "1") (pinfunction "1_1") (pintype "passive"))
      (node (ref "IC3") (pin "1") (pinfunction "BST_1") (pintype "input"))
    )
    (net (code "34") (name "Net-(IC3-FB)") (class "Default")
      (node (ref "C13") (pin "1") (pinfunction "1_1") (pintype "passive"))
      (node (ref "IC3") (pin "3") (pinfunction "FB_3") (pintype "input"))
      (node (ref "R7") (pin "2") (pinfunction "2_2") (pintype "passive"))
      (node (ref "R8") (pin "2") (pinfunction "2_2") (pintype "passive"))
    )
    (net (code "35") (name "Net-(IC7-RBIAS)") (class "Default")
      (node (ref "IC7") (pin "24") (pinfunction "RBIAS_24") (pintype "bidirectional"))
      (node (ref "R32") (pin "1") (pinfunction "1_1") (pintype "passive"))
    )
    (net (code "36") (name "Net-(IC7-RESERVED1)") (class "Default")
      (node (ref "IC7") (pin "21") (pinfunction "RESERVED1_21") (pintype "input"))
      (node (ref "R31") (pin "1") (pinfunction "1_1") (pintype "passive"))
    )
    (net (code "37") (name "Net-(IC7-RESERVED2)") (class "Default")
      (node (ref "IC7") (pin "20") (pinfunction "RESERVED2_20") (pintype "input"))
      (node (ref "R30") (pin "1") (pinfunction "1_1") (pintype "passive"))
    )
    (net (code "38") (name "Net-(IC7-RESET_N)") (class "Default")
      (node (ref "IC7") (pin "29") (pinfunction "RESET_N_29") (pintype "input"))
      (node (ref "R18") (pin "1") (pinfunction "1_1") (pintype "passive"))
    )
    (net (code "39") (name "Net-(IC7-RX_DV{slash}MDII_MODE)") (class "Default")
      (node (ref "IC7") (pin "39") (pinfunction "RX_DV/MDII_MODE_39") (pintype "bidirectional"))
      (node (ref "R20") (pin "2") (pinfunction "2_2") (pintype "passive"))
    )
    (net (code "40") (name "Net-(J1-PadG-)") (class "Default")
      (node (ref "J1") (pin "G-") (pinfunction "G-_G-") (pintype "bidirectional"))
      (node (ref "R29") (pin "1") (pinfunction "1_1") (pintype "passive"))
    )
    (net (code "41") (name "Net-(J1-PadY-)") (class "Default")
      (node (ref "J1") (pin "Y-") (pinfunction "Y-_Y-") (pintype "bidirectional"))
      (node (ref "R28") (pin "1") (pinfunction "1_1") (pintype "passive"))
    )
    (net (code "42") (name "Net-(JP2-Pad2)") (class "Default")
      (node (ref "JP2") (pin "2") (pinfunction "2_2") (pintype "passive"))
      (node (ref "R6") (pin "1") (pinfunction "1_1") (pintype "passive"))
    )
    (net (code "43") (name "Net-(LED1-PadA)") (class "Default")
      (node (ref "LED1") (pin "A") (pinfunction "A_A") (pintype "passive"))
      (node (ref "R21") (pin "2") (pinfunction "2_2") (pintype "passive"))
    )
    (net (code "44") (name "Net-(LED2-PadA)") (class "Default")
      (node (ref "LED2") (pin "A") (pinfunction "A_A") (pintype "passive"))
      (node (ref "R13") (pin "1") (pinfunction "1_1") (pintype "passive"))
    )
    (net (code "45") (name "Net-(LED3-PadA)") (class "Default")
      (node (ref "LED3") (pin "A") (pinfunction "A_A") (pintype "passive"))
      (node (ref "R14") (pin "2") (pinfunction "2_2") (pintype "passive"))
      (node (ref "R9") (pin "2") (pinfunction "2_2") (pintype "passive"))
    )
    (net (code "46") (name "Net-(R32-Pad2)") (class "Default")
      (node (ref "R32") (pin "2") (pinfunction "2_2") (pintype "passive"))
      (node (ref "R33") (pin "2") (pinfunction "2_2") (pintype "passive"))
    )
    (net (code "47") (name "Net-(R33-Pad1)") (class "Default")
      (node (ref "R33") (pin "1") (pinfunction "1_1") (pintype "passive"))
      (node (ref "R34") (pin "1") (pinfunction "1_1") (pintype "passive"))
    )
    (net (code "48") (name "Net-(U1-PIO1)") (class "Default")
      (node (ref "R9") (pin "1") (pinfunction "1_1") (pintype "passive"))
      (node (ref "U1") (pin "24") (pinfunction "PIO1_24") (pintype "bidirectional"))
    )
    (net (code "49") (name "Net-(U1-PIO8)") (class "Default")
      (node (ref "R14") (pin "1") (pinfunction "1_1") (pintype "passive"))
      (node (ref "U1") (pin "31") (pinfunction "PIO8_31") (pintype "bidirectional"))
    )
    (net (code "50") (name "Net-(U1-PIO9)") (class "Default")
      (node (ref "R13") (pin "2") (pinfunction "2_2") (pintype "passive"))
      (node (ref "U1") (pin "32") (pinfunction "PIO9_32") (pintype "bidirectional"))
    )
    (net (code "51") (name "Net-(U1-PIO11)") (class "Default")
      (node (ref "R15") (pin "2") (pinfunction "2_2") (pintype "passive"))
      (node (ref "R16") (pin "2") (pinfunction "2_2") (pintype "passive"))
      (node (ref "U1") (pin "34") (pinfunction "PIO11_34") (pintype "bidirectional"))
    )
    (net (code "52") (name "PC2") (class "Default")
      (node (ref "IC1") (pin "10") (pinfunction "PC2_10") (pintype "bidirectional"))
      (node (ref "X5") (pin "P$2") (pinfunction "2_P$2") (pintype "passive"))
    )
    (net (code "53") (name "PC3") (class "Default")
      (node (ref "IC1") (pin "11") (pinfunction "PC3_11") (pintype "bidirectional"))
      (node (ref "X5") (pin "P$1") (pinfunction "1_P$1") (pintype "passive"))
    )
    (net (code "54") (name "PC14") (class "Default")
      (node (ref "IC1") (pin "3") (pinfunction "PC14_3") (pintype "bidirectional"))
      (node (ref "X5") (pin "P$10") (pinfunction "10_P$10") (pintype "passive"))
    )
    (net (code "55") (name "PC15") (class "Default")
      (node (ref "IC1") (pin "4") (pinfunction "PC15_4") (pintype "bidirectional"))
      (node (ref "X5") (pin "P$9") (pinfunction "9_P$9") (pintype "passive"))
    )
    (net (code "56") (name "PFB") (class "Default")
      (node (ref "C32") (pin "1") (pinfunction "1_1") (pintype "passive"))
      (node (ref "C33") (pin "1") (pinfunction "1_1") (pintype "passive"))
      (node (ref "C34") (pin "1") (pinfunction "1_1") (pintype "passive"))
      (node (ref "C35") (pin "1") (pinfunction "1_1") (pintype "passive"))
      (node (ref "IC7") (pin "18") (pinfunction "PFBIN1_18") (pintype "power_in"))
      (node (ref "IC7") (pin "23") (pinfunction "PFBOUT_23") (pintype "output"))
      (node (ref "IC7") (pin "37") (pinfunction "PFBIN2_37") (pintype "power_in"))
    )
    (net (code "57") (name "RD+") (class "Default")
      (node (ref "IC7") (pin "14") (pinfunction "RD+_14") (pintype "bidirectional"))
      (node (ref "J1") (pin "RD+") (pinfunction "RD+_RD+") (pintype "bidirectional"))
      (node (ref "R26") (pin "2") (pinfunction "2_2") (pintype "passive"))
    )
    (net (code "58") (name "RD-") (class "Default")
      (node (ref "IC7") (pin "13") (pinfunction "RD-_13") (pintype "bidirectional"))
      (node (ref "J1") (pin "RD-") (pinfunction "RD-_RD-") (pintype "bidirectional"))
      (node (ref "R27") (pin "1") (pinfunction "1_1") (pintype "passive"))
    )
    (net (code "59") (name "RMII_CRS_DV") (class "Default")
      (node (ref "IC1") (pin "23") (pinfunction "PA7_23") (pintype "bidirectional"))
      (node (ref "IC7") (pin "40") (pinfunction "CRS/CRS_DV/LED_CFG_40") (pintype "bidirectional"))
      (node (ref "R19") (pin "2") (pinfunction "2_2") (pintype "passive"))
    )
    (net (code "60") (name "RMII_MDC") (class "Default")
      (node (ref "IC1") (pin "9") (pinfunction "PC1_9") (pintype "bidirectional"))
      (node (ref "IC7") (pin "31") (pinfunction "MDC_31") (pintype "input"))
    )
    (net (code "61") (name "RMII_MDIO") (class "Default")
      (node (ref "IC1") (pin "16") (pinfunction "PA2_16") (pintype "bidirectional"))
      (node (ref "IC7") (pin "30") (pinfunction "MDIO_30") (pintype "bidirectional"))
    )
    (net (code "62") (name "RMII_REF_CLK") (class "Default")
      (node (ref "IC1") (pin "15") (pinfunction "PA1_15") (pintype "bidirectional"))
      (node (ref "IC7") (pin "34") (pinfunction "X1_34") (pintype "input"))
      (node (ref "QG1") (pin "3") (pinfunction "OUT_3") (pintype "output"))
    )
    (net (code "63") (name "RMII_RXD0") (class "Default")
      (node (ref "IC1") (pin "24") (pinfunction "PC4_24") (pintype "bidirectional"))
      (node (ref "IC7") (pin "43") (pinfunction "RXD_0/PHYAD1_43") (pintype "bidirectional"))
    )
    (net (code "64") (name "RMII_RXD1") (class "Default")
      (node (ref "IC1") (pin "25") (pinfunction "PC5_25") (pintype "bidirectional"))
      (node (ref "IC7") (pin "44") (pinfunction "RXD_1/PHYAD2_44") (pintype "bidirectional"))
    )
    (net (code "65") (name "RMII_TXD0") (class "Default")
      (node (ref "IC1") (pin "33") (pinfunction "PB12_33") (pintype "bidirectional"))
      (node (ref "IC7") (pin "3") (pinfunction "TXD_0_3") (pintype "bidirectional"))
    )
    (net (code "66") (name "RMII_TXD1") (class "Default")
      (node (ref "IC1") (pin "34") (pinfunction "PB13_34") (pintype "bidirectional"))
      (node (ref "IC7") (pin "4") (pinfunction "TXD_1_4") (pintype "bidirectional"))
    )
    (net (code "67") (name "RMII_TX_EN") (class "Default")
      (node (ref "IC1") (pin "30") (pinfunction "PB11_30") (pintype "bidirectional"))
      (node (ref "IC7") (pin "2") (pinfunction "TX_EN_2") (pintype "bidirectional"))
    )
    (net (code "68") (name "SWCLK") (class "Default")
      (node (ref "IC1") (pin "49") (pinfunction "PA14_49") (pintype "bidirectional"))
      (node (ref "X2") (pin "2") (pinfunction "2_2") (pintype "passive"))
    )
    (net (code "69") (name "SWDIO") (class "Default")
      (node (ref "IC1") (pin "46") (pinfunction "PA13_46") (pintype "bidirectional"))
      (node (ref "X2") (pin "4") (pinfunction "4_4") (pintype "passive"))
    )
    (net (code "70") (name "TD+") (class "Default")
      (node (ref "IC7") (pin "17") (pinfunction "TD+_17") (pintype "bidirectional"))
      (node (ref "J1") (pin "TD+") (pinfunction "TD+_TD+") (pintype "bidirectional"))
      (node (ref "R24") (pin "2") (pinfunction "2_2") (pintype "passive"))
    )
    (net (code "71") (name "TD-") (class "Default")
      (node (ref "IC7") (pin "16") (pinfunction "TD-_16") (pintype "bidirectional"))
      (node (ref "J1") (pin "TD-") (pinfunction "TD-_TD-") (pintype "bidirectional"))
      (node (ref "R25") (pin "1") (pinfunction "1_1") (pintype "passive"))
    )
    (net (code "72") (name "TJA_EN") (class "Default")
      (node (ref "IC1") (pin "55") (pinfunction "PB3_55") (pintype "bidirectional"))
      (node (ref "IC2") (pin "6") (pinfunction "EN_6") (pintype "input"))
      (node (ref "R12") (pin "2") (pinfunction "2_2") (pintype "passive"))
    )
    (net (code "73") (name "TJA_ERR") (class "Default")
      (node (ref "IC1") (pin "59") (pinfunction "PB7_59") (pintype "bidirectional"))
      (node (ref "IC2") (pin "4") (pinfunction "ERR_4") (pintype "output"))
      (node (ref "R23") (pin "1") (pinfunction "1_1") (pintype "passive"))
    )
    (net (code "74") (name "TJA_INH") (class "Default")
      (node (ref "IC2") (pin "1") (pinfunction "INH_1") (pintype "output"))
      (node (ref "SW1") (pin "1") (pinfunction "1_1") (pintype "bidirectional"))
    )
    (net (code "75") (name "TJA_STB") (class "Default")
      (node (ref "IC1") (pin "56") (pinfunction "PB4_56") (pintype "bidirectional"))
      (node (ref "IC2") (pin "5") (pinfunction "STB_5") (pintype "input"))
      (node (ref "R11") (pin "2") (pinfunction "2_2") (pintype "passive"))
    )
    (net (code "76") (name "UART4_RX") (class "Default")
      (node (ref "IC1") (pin "52") (pinfunction "PC11_52") (pintype "bidirectional"))
      (node (ref "U1") (pin "1") (pinfunction "TX_1") (pintype "bidirectional"))
    )
    (net (code "77") (name "UART4_TX") (class "Default")
      (node (ref "IC1") (pin "51") (pinfunction "PC10_51") (pintype "bidirectional"))
      (node (ref "U1") (pin "2") (pinfunction "RX_2") (pintype "bidirectional"))
    )
    (net (code "78") (name "UART5_RX") (class "Default")
      (node (ref "IC1") (pin "54") (pinfunction "PD2_54") (pintype "bidirectional"))
      (node (ref "X5") (pin "P$15") (pinfunction "15_P$15") (pintype "passive"))
    )
    (net (code "79") (name "UART5_TX") (class "Default")
      (node (ref "IC1") (pin "53") (pinfunction "PC12_53") (pintype "bidirectional"))
      (node (ref "X5") (pin "P$7") (pinfunction "7_P$7") (pintype "passive"))
    )
    (net (code "80") (name "USB_D+") (class "Default")
      (node (ref "IC1") (pin "45") (pinfunction "PA12_45") (pintype "bidirectional"))
      (node (ref "X1") (pin "D+") (pinfunction "3_D+") (pintype "bidirectional"))
    )
    (net (code "81") (name "USB_D-") (class "Default")
      (node (ref "IC1") (pin "44") (pinfunction "PA11_44") (pintype "bidirectional"))
      (node (ref "X1") (pin "D-") (pinfunction "2_D-") (pintype "bidirectional"))
    )
    (net (code "82") (name "USB_VBUS") (class "Default")
      (node (ref "C41") (pin "1") (pinfunction "1_1") (pintype "passive"))
      (node (ref "D4") (pin "A") (pinfunction "A_A") (pintype "passive"))
      (node (ref "IC1") (pin "42") (pinfunction "PA9_42") (pintype "bidirectional"))
      (node (ref "X1") (pin "VBUS") (pinfunction "1_VBUS") (pintype "bidirectional"))
    )
    (net (code "83") (name "unconnected-(IC1A-PA0-WKUP-Pad14)") (class "Default")
      (node (ref "IC1") (pin "14") (pinfunction "PA0-WKUP_14") (pintype "bidirectional"))
    )
    (net (code "84") (name "unconnected-(IC1A-PA3-Pad17)") (class "Default")
      (node (ref "IC1") (pin "17") (pinfunction "PA3_17") (pintype "bidirectional"))
    )
    (net (code "85") (name "unconnected-(IC1A-PA4-Pad20)") (class "Default")
      (node (ref "IC1") (pin "20") (pinfunction "PA4_20") (pintype "bidirectional"))
    )
    (net (code "86") (name "unconnected-(IC1A-PA5-Pad21)") (class "Default")
      (node (ref "IC1") (pin "21") (pinfunction "PA5_21") (pintype "bidirectional"))
    )
    (net (code "87") (name "unconnected-(IC1A-PA6-Pad22)") (class "Default")
      (node (ref "IC1") (pin "22") (pinfunction "PA6_22") (pintype "bidirectional"))
    )
    (net (code "88") (name "unconnected-(IC1A-PA15-Pad50)") (class "Default")
      (node (ref "IC1") (pin "50") (pinfunction "PA15_50") (pintype "bidirectional"))
    )
    (net (code "89") (name "unconnected-(IC1A-PB0-Pad26)") (class "Default")
      (node (ref "IC1") (pin "26") (pinfunction "PB0_26") (pintype "bidirectional"))
    )
    (net (code "90") (name "unconnected-(IC1A-PB1-Pad27)") (class "Default")
      (node (ref "IC1") (pin "27") (pinfunction "PB1_27") (pintype "bidirectional"))
    )
    (net (code "91") (name "unconnected-(IC1A-PB10-Pad29)") (class "Default")
      (node (ref "IC1") (pin "29") (pinfunction "PB10_29") (pintype "bidirectional"))
    )
    (net (code "92") (name "unconnected-(IC1A-PB15-Pad36)") (class "Default")
      (node (ref "IC1") (pin "36") (pinfunction "PB15_36") (pintype "bidirectional"))
    )
    (net (code "93") (name "unconnected-(IC1A-PC0-Pad8)") (class "Default")
      (node (ref "IC1") (pin "8") (pinfunction "PC0_8") (pintype "bidirectional"))
    )
    (net (code "94") (name "unconnected-(IC1A-PC6-Pad37)") (class "Default")
      (node (ref "IC1") (pin "37") (pinfunction "PC6_37") (pintype "bidirectional"))
    )
    (net (code "95") (name "unconnected-(IC1A-PC7-Pad38)") (class "Default")
      (node (ref "IC1") (pin "38") (pinfunction "PC7_38") (pintype "bidirectional"))
    )
    (net (code "96") (name "unconnected-(IC1A-PC8-Pad39)") (class "Default")
      (node (ref "IC1") (pin "39") (pinfunction "PC8_39") (pintype "bidirectional"))
    )
    (net (code "97") (name "unconnected-(IC1A-PC9-Pad40)") (class "Default")
      (node (ref "IC1") (pin "40") (pinfunction "PC9_40") (pintype "bidirectional"))
    )
    (net (code "98") (name "unconnected-(IC7-CLK_OUT-Pad25)") (class "Default")
      (node (ref "IC7") (pin "25") (pinfunction "CLK_OUT_25") (pintype "bidirectional"))
    )
    (net (code "99") (name "unconnected-(IC7-COL{slash}PHYAD1-Pad42)") (class "Default")
      (node (ref "IC7") (pin "42") (pinfunction "COL/PHYAD1_42") (pintype "bidirectional"))
    )
    (net (code "100") (name "unconnected-(IC7-LED_SPEED{slash}AN1-Pad27)") (class "Default")
      (node (ref "IC7") (pin "27") (pinfunction "LED_SPEED/AN1_27") (pintype "bidirectional"))
    )
    (net (code "101") (name "unconnected-(IC7-PWR_DOWN{slash}INTN-Pad7)") (class "Default")
      (node (ref "IC7") (pin "7") (pinfunction "PWR_DOWN/INTN_7") (pintype "bidirectional"))
    )
    (net (code "102") (name "unconnected-(IC7-RXD_2{slash}PHYAD3-Pad45)") (class "Default")
      (node (ref "IC7") (pin "45") (pinfunction "RXD_2/PHYAD3_45") (pintype "bidirectional"))
    )
    (net (code "103") (name "unconnected-(IC7-RXD_3{slash}PHYAD4-Pad46)") (class "Default")
      (node (ref "IC7") (pin "46") (pinfunction "RXD_3/PHYAD4_46") (pintype "bidirectional"))
    )
    (net (code "104") (name "unconnected-(IC7-RX_CLK-Pad38)") (class "Default")
      (node (ref "IC7") (pin "38") (pinfunction "RX_CLK_38") (pintype "bidirectional"))
    )
    (net (code "105") (name "unconnected-(IC7-RX_ER{slash}MDIX_ER-Pad41)") (class "Default")
      (node (ref "IC7") (pin "41") (pinfunction "RX_ER/MDIX_ER_41") (pintype "bidirectional"))
    )
    (net (code "106") (name "unconnected-(IC7-TCK-Pad8)") (class "Default")
      (node (ref "IC7") (pin "8") (pinfunction "TCK_8") (pintype "input"))
    )
    (net (code "107") (name "unconnected-(IC7-TDI-Pad12)") (class "Default")
      (node (ref "IC7") (pin "12") (pinfunction "TDI_12") (pintype "input"))
    )
    (net (code "108") (name "unconnected-(IC7-TDO-Pad9)") (class "Default")
      (node (ref "IC7") (pin "9") (pinfunction "TDO_9") (pintype "output"))
    )
    (net (code "109") (name "unconnected-(IC7-TMS-Pad10)") (class "Default")
      (node (ref "IC7") (pin "10") (pinfunction "TMS_10") (pintype "input"))
    )
    (net (code "110") (name "unconnected-(IC7-TRST_N-Pad11)") (class "Default")
      (node (ref "IC7") (pin "11") (pinfunction "TRST_N_11") (pintype "input"))
    )
    (net (code "111") (name "unconnected-(IC7-TXD_2-Pad5)") (class "Default")
      (node (ref "IC7") (pin "5") (pinfunction "TXD_2_5") (pintype "bidirectional"))
    )
    (net (code "112") (name "unconnected-(IC7-TXD_3{slash}SNI_MODE-Pad6)") (class "Default")
      (node (ref "IC7") (pin "6") (pinfunction "TXD_3/SNI_MODE_6") (pintype "bidirectional"))
    )
    (net (code "113") (name "unconnected-(IC7-TX_CLK-Pad1)") (class "Default")
      (node (ref "IC7") (pin "1") (pinfunction "TX_CLK_1") (pintype "bidirectional"))
    )
    (net (code "114") (name "unconnected-(IC7-X2-Pad33)") (class "Default")
      (node (ref "IC7") (pin "33") (pinfunction "X2_33") (pintype "output"))
    )
    (net (code "115") (name "unconnected-(J1-PadNC)") (class "Default")
      (node (ref "J1") (pin "NC") (pinfunction "NC_NC") (pintype "bidirectional"))
    )
    (net (code "116") (name "unconnected-(QG1-E{slash}D-Pad1)") (class "Default")
      (node (ref "QG1") (pin "1") (pinfunction "E/D_1") (pintype "input"))
    )
    (net (code "117") (name "unconnected-(SW2-Pad3)") (class "Default")
      (node (ref "SW2") (pin "3") (pinfunction "3_3") (pintype "bidirectional"))
    )
    (net (code "118") (name "unconnected-(U1-AIO0-Pad9)") (class "Default")
      (node (ref "U1") (pin "9") (pinfunction "AIO0_9") (pintype "bidirectional"))
    )
    (net (code "119") (name "unconnected-(U1-AIO1-Pad10)") (class "Default")
      (node (ref "U1") (pin "10") (pinfunction "AIO1_10") (pintype "bidirectional"))
    )
    (net (code "120") (name "unconnected-(U1-CLK-Pad19)") (class "Default")
      (node (ref "U1") (pin "19") (pinfunction "CLK_19") (pintype "bidirectional"))
    )
    (net (code "121") (name "unconnected-(U1-CSB-Pad16)") (class "Default")
      (node (ref "U1") (pin "16") (pinfunction "CSB_16") (pintype "bidirectional"))
    )
    (net (code "122") (name "unconnected-(U1-CTS-Pad3)") (class "Default")
      (node (ref "U1") (pin "3") (pinfunction "CTS_3") (pintype "bidirectional"))
    )
    (net (code "123") (name "unconnected-(U1-MISO-Pad18)") (class "Default")
      (node (ref "U1") (pin "18") (pinfunction "MISO_18") (pintype "bidirectional"))
    )
    (net (code "124") (name "unconnected-(U1-MOSI-Pad17)") (class "Default")
      (node (ref "U1") (pin "17") (pinfunction "MOSI_17") (pintype "bidirectional"))
    )
    (net (code "125") (name "unconnected-(U1-NC-Pad14)") (class "Default")
      (node (ref "U1") (pin "14") (pinfunction "NC_14") (pintype "bidirectional"))
    )
    (net (code "126") (name "unconnected-(U1-PCM_CLK-Pad5)") (class "Default")
      (node (ref "U1") (pin "5") (pinfunction "PCM_CLK_5") (pintype "bidirectional"))
    )
    (net (code "127") (name "unconnected-(U1-PCM_IN-Pad7)") (class "Default")
      (node (ref "U1") (pin "7") (pinfunction "PCM_IN_7") (pintype "bidirectional"))
    )
    (net (code "128") (name "unconnected-(U1-PCM_OUT-Pad6)") (class "Default")
      (node (ref "U1") (pin "6") (pinfunction "PCM_OUT_6") (pintype "bidirectional"))
    )
    (net (code "129") (name "unconnected-(U1-PCN_SYNC-Pad8)") (class "Default")
      (node (ref "U1") (pin "8") (pinfunction "PCN_SYNC_8") (pintype "bidirectional"))
    )
    (net (code "130") (name "unconnected-(U1-PIO0-Pad23)") (class "Default")
      (node (ref "U1") (pin "23") (pinfunction "PIO0_23") (pintype "bidirectional"))
    )
    (net (code "131") (name "unconnected-(U1-PIO2-Pad25)") (class "Default")
      (node (ref "U1") (pin "25") (pinfunction "PIO2_25") (pintype "bidirectional"))
    )
    (net (code "132") (name "unconnected-(U1-PIO3-Pad26)") (class "Default")
      (node (ref "U1") (pin "26") (pinfunction "PIO3_26") (pintype "bidirectional"))
    )
    (net (code "133") (name "unconnected-(U1-PIO4-Pad27)") (class "Default")
      (node (ref "U1") (pin "27") (pinfunction "PIO4_27") (pintype "bidirectional"))
    )
    (net (code "134") (name "unconnected-(U1-PIO5-Pad28)") (class "Default")
      (node (ref "U1") (pin "28") (pinfunction "PIO5_28") (pintype "bidirectional"))
    )
    (net (code "135") (name "unconnected-(U1-PIO6-Pad29)") (class "Default")
      (node (ref "U1") (pin "29") (pinfunction "PIO6_29") (pintype "bidirectional"))
    )
    (net (code "136") (name "unconnected-(U1-PIO7-Pad30)") (class "Default")
      (node (ref "U1") (pin "30") (pinfunction "PIO7_30") (pintype "bidirectional"))
    )
    (net (code "137") (name "unconnected-(U1-PIO10-Pad33)") (class "Default")
      (node (ref "U1") (pin "33") (pinfunction "PIO10_33") (pintype "bidirectional"))
    )
    (net (code "138") (name "unconnected-(U1-RTS-Pad4)") (class "Default")
      (node (ref "U1") (pin "4") (pinfunction "RTS_4") (pintype "bidirectional"))
    )
    (net (code "139") (name "unconnected-(U1-VBUSD+-Pad20)") (class "Default")
      (node (ref "U1") (pin "20") (pinfunction "VBUSD+_20") (pintype "bidirectional"))
    )
    (net (code "140") (name "unconnected-(U1-VBUSD--Pad15)") (class "Default")
      (node (ref "U1") (pin "15") (pinfunction "VBUSD-_15") (pintype "bidirectional"))
    )
  )
)
